# GL852-0.net
KiCad netlist of a schematic drawn in Altium Designer
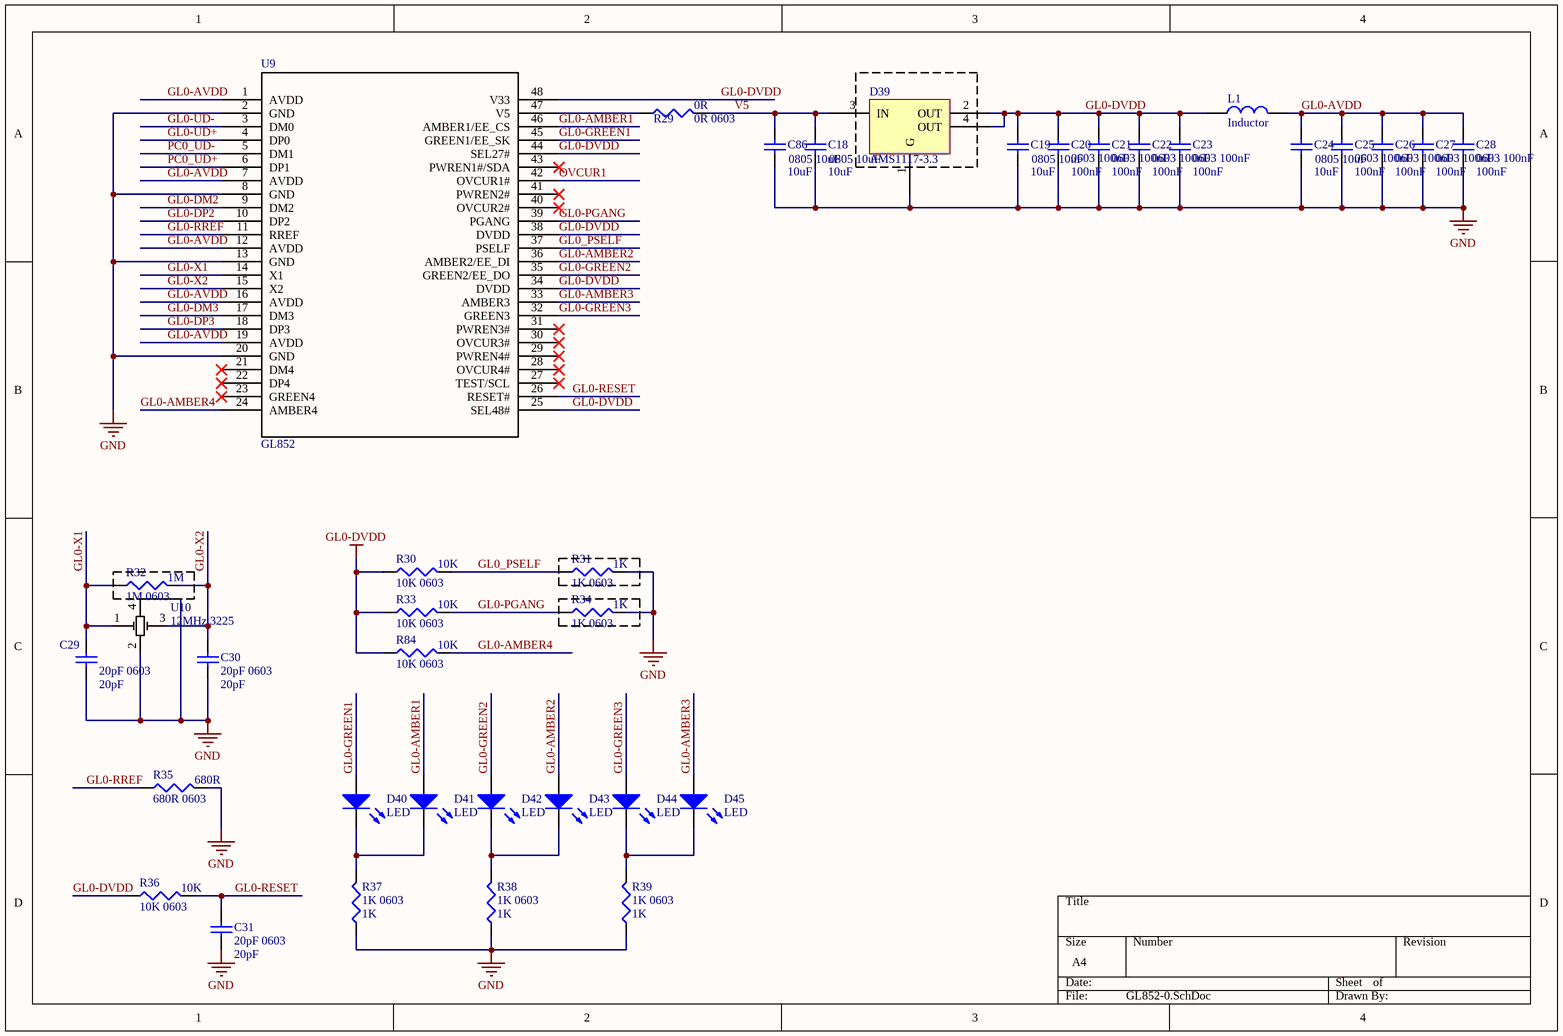
[diagram p0: GL852-0.SchDoc]

(export (version "E")
  (design (tool "Eeschema 10.0.6"))
  (components
    (comp (ref "C18")
      (value "0805 10uF")
      (footprint "C0805")
      (description "Capacitor (Semiconductor SIM Model)")
      (fields (field (name "ALTIUM_VALUE") "10uF") (field (name "PUBLISHER") "Altium Limited"))
      (libsource (lib "Miscellaneous Devices") (part "Cap Semi"))
    )
    (comp (ref "C19")
      (value "0805 10uF")
      (footprint "C0805")
      (description "Capacitor (Semiconductor SIM Model)")
      (fields (field (name "ALTIUM_VALUE") "10uF") (field (name "PUBLISHER") "Altium Limited"))
      (libsource (lib "Miscellaneous Devices") (part "Cap Semi"))
    )
    (comp (ref "C20")
      (value "0603 100nF")
      (footprint "C0603")
      (description "Capacitor (Semiconductor SIM Model)")
      (fields (field (name "ALTIUM_VALUE") "100nF") (field (name "PUBLISHER") "Altium Limited"))
      (libsource (lib "Miscellaneous Devices") (part "Cap Semi"))
    )
    (comp (ref "C21")
      (value "0603 100nF")
      (footprint "C0603")
      (description "Capacitor (Semiconductor SIM Model)")
      (fields (field (name "ALTIUM_VALUE") "100nF") (field (name "PUBLISHER") "Altium Limited"))
      (libsource (lib "Miscellaneous Devices") (part "Cap Semi"))
    )
    (comp (ref "C22")
      (value "0603 100nF")
      (footprint "C0603")
      (description "Capacitor (Semiconductor SIM Model)")
      (fields (field (name "ALTIUM_VALUE") "100nF") (field (name "PUBLISHER") "Altium Limited"))
      (libsource (lib "Miscellaneous Devices") (part "Cap Semi"))
    )
    (comp (ref "C23")
      (value "0603 100nF")
      (footprint "C0603")
      (description "Capacitor (Semiconductor SIM Model)")
      (fields (field (name "ALTIUM_VALUE") "100nF") (field (name "PUBLISHER") "Altium Limited"))
      (libsource (lib "Miscellaneous Devices") (part "Cap Semi"))
    )
    (comp (ref "C24")
      (value "0805 10uF")
      (footprint "C0805")
      (description "Capacitor (Semiconductor SIM Model)")
      (fields (field (name "ALTIUM_VALUE") "10uF") (field (name "PUBLISHER") "Altium Limited"))
      (libsource (lib "Miscellaneous Devices") (part "Cap Semi"))
    )
    (comp (ref "C25")
      (value "0603 100nF")
      (footprint "C0603")
      (description "Capacitor (Semiconductor SIM Model)")
      (fields (field (name "ALTIUM_VALUE") "100nF") (field (name "PUBLISHER") "Altium Limited"))
      (libsource (lib "Miscellaneous Devices") (part "Cap Semi"))
    )
    (comp (ref "C26")
      (value "0603 100nF")
      (footprint "C0603")
      (description "Capacitor (Semiconductor SIM Model)")
      (fields (field (name "ALTIUM_VALUE") "100nF") (field (name "PUBLISHER") "Altium Limited"))
      (libsource (lib "Miscellaneous Devices") (part "Cap Semi"))
    )
    (comp (ref "C27")
      (value "0603 100nF")
      (footprint "C0603")
      (description "Capacitor (Semiconductor SIM Model)")
      (fields (field (name "ALTIUM_VALUE") "100nF") (field (name "PUBLISHER") "Altium Limited"))
      (libsource (lib "Miscellaneous Devices") (part "Cap Semi"))
    )
    (comp (ref "C28")
      (value "0603 100nF")
      (footprint "C0603")
      (description "Capacitor (Semiconductor SIM Model)")
      (fields (field (name "ALTIUM_VALUE") "100nF") (field (name "PUBLISHER") "Altium Limited"))
      (libsource (lib "Miscellaneous Devices") (part "Cap Semi"))
    )
    (comp (ref "C29")
      (value "20pF 0603")
      (footprint "C0603")
      (description "Capacitor (Semiconductor SIM Model)")
      (fields (field (name "ALTIUM_VALUE") "20pF") (field (name "PUBLISHER") "Altium Limited"))
      (libsource (lib "Miscellaneous Devices") (part "Cap Semi"))
    )
    (comp (ref "C30")
      (value "20pF 0603")
      (footprint "C0603")
      (description "Capacitor (Semiconductor SIM Model)")
      (fields (field (name "ALTIUM_VALUE") "20pF") (field (name "PUBLISHER") "Altium Limited"))
      (libsource (lib "Miscellaneous Devices") (part "Cap Semi"))
    )
    (comp (ref "C31")
      (value "20pF 0603")
      (footprint "C0603")
      (description "Capacitor (Semiconductor SIM Model)")
      (fields (field (name "ALTIUM_VALUE") "20pF") (field (name "PUBLISHER") "Altium Limited"))
      (libsource (lib "Miscellaneous Devices") (part "Cap Semi"))
    )
    (comp (ref "C86")
      (value "0805 10uF")
      (footprint "C0805")
      (description "Capacitor (Semiconductor SIM Model)")
      (fields (field (name "ALTIUM_VALUE") "10uF") (field (name "PUBLISHER") "Altium Limited"))
      (libsource (lib "Miscellaneous Devices") (part "Cap Semi"))
    )
    (comp (ref "D39")
      (value "AMS1117-3.3")
      (footprint "SOT-223")
      (libsource (lib "MyLib") (part "AMS1117-3.3"))
    )
    (comp (ref "D40") (value "LED") (footprint "LED0603") (libsource (lib "Common Device") (part "LED")))
    (comp (ref "D41") (value "LED") (footprint "LED0603") (libsource (lib "Common Device") (part "LED")))
    (comp (ref "D42") (value "LED") (footprint "LED0603") (libsource (lib "Common Device") (part "LED")))
    (comp (ref "D43") (value "LED") (footprint "LED0603") (libsource (lib "Common Device") (part "LED")))
    (comp (ref "D44") (value "LED") (footprint "LED0603") (libsource (lib "Common Device") (part "LED")))
    (comp (ref "D45") (value "LED") (footprint "LED0603") (libsource (lib "Common Device") (part "LED")))
    (comp (ref "L1")
      (value "Inductor")
      (footprint "L0603")
      (libsource (lib "Common Device") (part "Inductor"))
    )
    (comp (ref "R29")
      (value "0R 0603")
      (footprint "R0603")
      (description "Resistor")
      (fields (field (name "ALTIUM_VALUE") "0R") (field (name "PUBLISHER") "Altium Limited"))
      (libsource (lib "Miscellaneous Devices") (part "Res3"))
    )
    (comp (ref "R30")
      (value "10K 0603")
      (footprint "R0603")
      (description "Resistor")
      (fields (field (name "ALTIUM_VALUE") "10K") (field (name "PUBLISHER") "Altium Limited"))
      (libsource (lib "Miscellaneous Devices") (part "Res3"))
    )
    (comp (ref "R31")
      (value "1K 0603")
      (footprint "R0603")
      (description "Resistor")
      (fields (field (name "ALTIUM_VALUE") "1K") (field (name "PUBLISHER") "Altium Limited"))
      (libsource (lib "Miscellaneous Devices") (part "Res3"))
    )
    (comp (ref "R32")
      (value "1M 0603")
      (footprint "R0603")
      (description "Resistor")
      (fields (field (name "ALTIUM_VALUE") "1M") (field (name "PUBLISHER") "Altium Limited"))
      (libsource (lib "Miscellaneous Devices") (part "Res3"))
    )
    (comp (ref "R33")
      (value "10K 0603")
      (footprint "R0603")
      (description "Resistor")
      (fields (field (name "ALTIUM_VALUE") "10K") (field (name "PUBLISHER") "Altium Limited"))
      (libsource (lib "Miscellaneous Devices") (part "Res3"))
    )
    (comp (ref "R34")
      (value "1K 0603")
      (footprint "R0603")
      (description "Resistor")
      (fields (field (name "ALTIUM_VALUE") "1K") (field (name "PUBLISHER") "Altium Limited"))
      (libsource (lib "Miscellaneous Devices") (part "Res3"))
    )
    (comp (ref "R35")
      (value "680R 0603")
      (footprint "R0603")
      (description "Resistor")
      (fields (field (name "ALTIUM_VALUE") "680R") (field (name "PUBLISHER") "Altium Limited"))
      (libsource (lib "Miscellaneous Devices") (part "Res3"))
    )
    (comp (ref "R36")
      (value "10K 0603")
      (footprint "R0603")
      (description "Resistor")
      (fields (field (name "ALTIUM_VALUE") "10K") (field (name "PUBLISHER") "Altium Limited"))
      (libsource (lib "Miscellaneous Devices") (part "Res3"))
    )
    (comp (ref "R37")
      (value "1K 0603")
      (footprint "R0603")
      (description "Resistor")
      (fields (field (name "ALTIUM_VALUE") "1K") (field (name "PUBLISHER") "Altium Limited"))
      (libsource (lib "Miscellaneous Devices") (part "Res3"))
    )
    (comp (ref "R38")
      (value "1K 0603")
      (footprint "R0603")
      (description "Resistor")
      (fields (field (name "ALTIUM_VALUE") "1K") (field (name "PUBLISHER") "Altium Limited"))
      (libsource (lib "Miscellaneous Devices") (part "Res3"))
    )
    (comp (ref "R39")
      (value "1K 0603")
      (footprint "R0603")
      (description "Resistor")
      (fields (field (name "ALTIUM_VALUE") "1K") (field (name "PUBLISHER") "Altium Limited"))
      (libsource (lib "Miscellaneous Devices") (part "Res3"))
    )
    (comp (ref "R84")
      (value "10K 0603")
      (footprint "R0603")
      (description "Resistor")
      (fields (field (name "ALTIUM_VALUE") "10K") (field (name "PUBLISHER") "Altium Limited"))
      (libsource (lib "Miscellaneous Devices") (part "Res3"))
    )
    (comp (ref "U9")
      (value "GL852")
      (footprint "qfp48-20-0909b")
      (description "Imported")
      (libsource (lib "USB-new-component") (part "GL852"))
    )
    (comp (ref "U10")
      (value "12MHz 3225")
      (footprint "XTAL-3225")
      (libsource (lib "XTAL3225") (part "Component_1"))
    )
  )
  (nets
    (net (code "1") (name "/GL0-AMBER1") (class "Default")
      (node (ref "D41") (pin "1") (pinfunction "A_1") (pintype "passive"))
      (node (ref "U9") (pin "46") (pinfunction "AMBER1/EE_CS_46") (pintype "passive"))
    )
    (net (code "2") (name "/GL0-AMBER2") (class "Default")
      (node (ref "D43") (pin "1") (pinfunction "A_1") (pintype "passive"))
      (node (ref "U9") (pin "36") (pinfunction "AMBER2/EE_DI_36") (pintype "passive"))
    )
    (net (code "3") (name "/GL0-AMBER3") (class "Default")
      (node (ref "D45") (pin "1") (pinfunction "A_1") (pintype "passive"))
      (node (ref "U9") (pin "33") (pinfunction "AMBER3_33") (pintype "passive"))
    )
    (net (code "4") (name "/GL0-AMBER4") (class "Default")
      (node (ref "R84") (pin "2") (pinfunction "2_2") (pintype "passive"))
      (node (ref "U9") (pin "24") (pinfunction "AMBER4_24") (pintype "passive"))
    )
    (net (code "5") (name "/GL0-AVDD") (class "Default")
      (node (ref "C24") (pin "2") (pinfunction "2_2") (pintype "passive"))
      (node (ref "C25") (pin "2") (pinfunction "2_2") (pintype "passive"))
      (node (ref "C26") (pin "2") (pinfunction "2_2") (pintype "passive"))
      (node (ref "C27") (pin "2") (pinfunction "2_2") (pintype "passive"))
      (node (ref "C28") (pin "2") (pinfunction "2_2") (pintype "passive"))
      (node (ref "L1") (pin "2") (pinfunction "2_2") (pintype "passive"))
      (node (ref "U9") (pin "1") (pinfunction "AVDD_1") (pintype "passive"))
      (node (ref "U9") (pin "12") (pinfunction "AVDD_12") (pintype "passive"))
      (node (ref "U9") (pin "16") (pinfunction "AVDD_16") (pintype "passive"))
      (node (ref "U9") (pin "19") (pinfunction "AVDD_19") (pintype "passive"))
      (node (ref "U9") (pin "7") (pinfunction "AVDD_7") (pintype "passive"))
    )
    (net (code "6") (name "/GL0-DM2") (class "Default")
      (node (ref "U9") (pin "9") (pinfunction "DM2_9") (pintype "passive"))
    )
    (net (code "7") (name "/GL0-DM3") (class "Default")
      (node (ref "U9") (pin "17") (pinfunction "DM3_17") (pintype "passive"))
    )
    (net (code "8") (name "/GL0-DP2") (class "Default")
      (node (ref "U9") (pin "10") (pinfunction "DP2_10") (pintype "passive"))
    )
    (net (code "9") (name "/GL0-DP3") (class "Default")
      (node (ref "U9") (pin "18") (pinfunction "DP3_18") (pintype "passive"))
    )
    (net (code "10") (name "/GL0-GREEN1") (class "Default")
      (node (ref "D40") (pin "1") (pinfunction "A_1") (pintype "passive"))
      (node (ref "U9") (pin "45") (pinfunction "GREEN1/EE_SK_45") (pintype "passive"))
    )
    (net (code "11") (name "/GL0-GREEN2") (class "Default")
      (node (ref "D42") (pin "1") (pinfunction "A_1") (pintype "passive"))
      (node (ref "U9") (pin "35") (pinfunction "GREEN2/EE_DO_35") (pintype "passive"))
    )
    (net (code "12") (name "/GL0-GREEN3") (class "Default")
      (node (ref "D44") (pin "1") (pinfunction "A_1") (pintype "passive"))
      (node (ref "U9") (pin "32") (pinfunction "GREEN3_32") (pintype "passive"))
    )
    (net (code "13") (name "/GL0-PGANG") (class "Default")
      (node (ref "R33") (pin "2") (pinfunction "2_2") (pintype "passive"))
      (node (ref "R34") (pin "1") (pinfunction "1_1") (pintype "passive"))
      (node (ref "U9") (pin "39") (pinfunction "PGANG_39") (pintype "passive"))
    )
    (net (code "14") (name "/GL0-RESET") (class "Default")
      (node (ref "C31") (pin "2") (pinfunction "2_2") (pintype "passive"))
      (node (ref "R36") (pin "2") (pinfunction "2_2") (pintype "passive"))
      (node (ref "U9") (pin "26") (pinfunction "RESET#_26") (pintype "passive"))
    )
    (net (code "15") (name "/GL0-RREF") (class "Default")
      (node (ref "R35") (pin "1") (pinfunction "1_1") (pintype "passive"))
      (node (ref "U9") (pin "11") (pinfunction "RREF_11") (pintype "passive"))
    )
    (net (code "16") (name "/GL0-UD+") (class "Default")
      (node (ref "U9") (pin "4") (pinfunction "DP0_4") (pintype "passive"))
    )
    (net (code "17") (name "/GL0-UD-") (class "Default")
      (node (ref "U9") (pin "3") (pinfunction "DM0_3") (pintype "passive"))
    )
    (net (code "18") (name "/GL0-X1") (class "Default")
      (node (ref "C29") (pin "2") (pinfunction "2_2") (pintype "passive"))
      (node (ref "R32") (pin "1") (pinfunction "1_1") (pintype "passive"))
      (node (ref "U10") (pin "1") (pinfunction "1_1") (pintype "passive"))
      (node (ref "U9") (pin "14") (pinfunction "X1_14") (pintype "passive"))
    )
    (net (code "19") (name "/GL0-X2") (class "Default")
      (node (ref "C30") (pin "2") (pinfunction "2_2") (pintype "passive"))
      (node (ref "R32") (pin "2") (pinfunction "2_2") (pintype "passive"))
      (node (ref "U10") (pin "3") (pinfunction "3_3") (pintype "passive"))
      (node (ref "U9") (pin "15") (pinfunction "X2_15") (pintype "passive"))
    )
    (net (code "20") (name "/GL0_PSELF") (class "Default")
      (node (ref "R30") (pin "2") (pinfunction "2_2") (pintype "passive"))
      (node (ref "R31") (pin "1") (pinfunction "1_1") (pintype "passive"))
      (node (ref "U9") (pin "37") (pinfunction "PSELF_37") (pintype "passive"))
    )
    (net (code "21") (name "/OVCUR1") (class "Default")
      (node (ref "U9") (pin "42") (pinfunction "OVCUR1#_42") (pintype "passive"))
    )
    (net (code "22") (name "/PC0_UD+") (class "Default")
      (node (ref "U9") (pin "6") (pinfunction "DP1_6") (pintype "passive"))
    )
    (net (code "23") (name "/PC0_UD-") (class "Default")
      (node (ref "U9") (pin "5") (pinfunction "DM1_5") (pintype "passive"))
    )
    (net (code "24") (name "/V5") (class "Default")
      (node (ref "C18") (pin "2") (pinfunction "2_2") (pintype "passive"))
      (node (ref "C86") (pin "2") (pinfunction "2_2") (pintype "passive"))
      (node (ref "D39") (pin "3") (pinfunction "IN_3") (pintype "passive"))
      (node (ref "R29") (pin "2") (pinfunction "2_2") (pintype "passive"))
    )
    (net (code "25") (name "GL0-DVDD") (class "Default")
      (node (ref "C19") (pin "2") (pinfunction "2_2") (pintype "passive"))
      (node (ref "C20") (pin "2") (pinfunction "2_2") (pintype "passive"))
      (node (ref "C21") (pin "2") (pinfunction "2_2") (pintype "passive"))
      (node (ref "C22") (pin "2") (pinfunction "2_2") (pintype "passive"))
      (node (ref "C23") (pin "2") (pinfunction "2_2") (pintype "passive"))
      (node (ref "D39") (pin "2") (pinfunction "OUT_2") (pintype "passive"))
      (node (ref "D39") (pin "4") (pinfunction "OUT_4") (pintype "passive"))
      (node (ref "L1") (pin "1") (pinfunction "1_1") (pintype "passive"))
      (node (ref "R30") (pin "1") (pinfunction "1_1") (pintype "passive"))
      (node (ref "R33") (pin "1") (pinfunction "1_1") (pintype "passive"))
      (node (ref "R36") (pin "1") (pinfunction "1_1") (pintype "passive"))
      (node (ref "R84") (pin "1") (pinfunction "1_1") (pintype "passive"))
      (node (ref "U9") (pin "25") (pinfunction "SEL48#_25") (pintype "passive"))
      (node (ref "U9") (pin "34") (pinfunction "DVDD_34") (pintype "passive"))
      (node (ref "U9") (pin "38") (pinfunction "DVDD_38") (pintype "passive"))
      (node (ref "U9") (pin "44") (pinfunction "SEL27#_44") (pintype "passive"))
      (node (ref "U9") (pin "48") (pinfunction "V33_48") (pintype "passive"))
    )
    (net (code "26") (name "GND") (class "Default")
      (node (ref "C18") (pin "1") (pinfunction "1_1") (pintype "passive"))
      (node (ref "C19") (pin "1") (pinfunction "1_1") (pintype "passive"))
      (node (ref "C20") (pin "1") (pinfunction "1_1") (pintype "passive"))
      (node (ref "C21") (pin "1") (pinfunction "1_1") (pintype "passive"))
      (node (ref "C22") (pin "1") (pinfunction "1_1") (pintype "passive"))
      (node (ref "C23") (pin "1") (pinfunction "1_1") (pintype "passive"))
      (node (ref "C24") (pin "1") (pinfunction "1_1") (pintype "passive"))
      (node (ref "C25") (pin "1") (pinfunction "1_1") (pintype "passive"))
      (node (ref "C26") (pin "1") (pinfunction "1_1") (pintype "passive"))
      (node (ref "C27") (pin "1") (pinfunction "1_1") (pintype "passive"))
      (node (ref "C28") (pin "1") (pinfunction "1_1") (pintype "passive"))
      (node (ref "C29") (pin "1") (pinfunction "1_1") (pintype "passive"))
      (node (ref "C30") (pin "1") (pinfunction "1_1") (pintype "passive"))
      (node (ref "C31") (pin "1") (pinfunction "1_1") (pintype "passive"))
      (node (ref "C86") (pin "1") (pinfunction "1_1") (pintype "passive"))
      (node (ref "D39") (pin "1") (pinfunction "G_1") (pintype "passive"))
      (node (ref "R31") (pin "2") (pinfunction "2_2") (pintype "passive"))
      (node (ref "R34") (pin "2") (pinfunction "2_2") (pintype "passive"))
      (node (ref "R35") (pin "2") (pinfunction "2_2") (pintype "passive"))
      (node (ref "R37") (pin "1") (pinfunction "1_1") (pintype "passive"))
      (node (ref "R38") (pin "1") (pinfunction "1_1") (pintype "passive"))
      (node (ref "R39") (pin "1") (pinfunction "1_1") (pintype "passive"))
      (node (ref "U10") (pin "2") (pinfunction "2_2") (pintype "passive"))
      (node (ref "U10") (pin "4") (pinfunction "4_4") (pintype "passive"))
      (node (ref "U9") (pin "13") (pinfunction "GND_13") (pintype "passive"))
      (node (ref "U9") (pin "2") (pinfunction "GND_2") (pintype "passive"))
      (node (ref "U9") (pin "20") (pinfunction "GND_20") (pintype "passive"))
      (node (ref "U9") (pin "8") (pinfunction "GND_8") (pintype "passive"))
    )
    (net (code "27") (name "Net-(D40-K)") (class "Default")
      (node (ref "D40") (pin "2") (pinfunction "K_2") (pintype "passive"))
      (node (ref "D41") (pin "2") (pinfunction "K_2") (pintype "passive"))
      (node (ref "R37") (pin "2") (pinfunction "2_2") (pintype "passive"))
    )
    (net (code "28") (name "Net-(D42-K)") (class "Default")
      (node (ref "D42") (pin "2") (pinfunction "K_2") (pintype "passive"))
      (node (ref "D43") (pin "2") (pinfunction "K_2") (pintype "passive"))
      (node (ref "R38") (pin "2") (pinfunction "2_2") (pintype "passive"))
    )
    (net (code "29") (name "Net-(D44-K)") (class "Default")
      (node (ref "D44") (pin "2") (pinfunction "K_2") (pintype "passive"))
      (node (ref "D45") (pin "2") (pinfunction "K_2") (pintype "passive"))
      (node (ref "R39") (pin "2") (pinfunction "2_2") (pintype "passive"))
    )
    (net (code "30") (name "Net-(U9-V5)") (class "Default")
      (node (ref "R29") (pin "1") (pinfunction "1_1") (pintype "passive"))
      (node (ref "U9") (pin "47") (pinfunction "V5_47") (pintype "passive"))
    )
    (net (code "31") (name "unconnected-(U9-DM4-Pad21)") (class "Default")
      (node (ref "U9") (pin "21") (pinfunction "DM4_21") (pintype "passive+no_connect"))
    )
    (net (code "32") (name "unconnected-(U9-DP4-Pad22)") (class "Default")
      (node (ref "U9") (pin "22") (pinfunction "DP4_22") (pintype "passive+no_connect"))
    )
    (net (code "33") (name "unconnected-(U9-GREEN4-Pad23)") (class "Default")
      (node (ref "U9") (pin "23") (pinfunction "GREEN4_23") (pintype "passive+no_connect"))
    )
    (net (code "34") (name "unconnected-(U9-OVCUR2#-Pad40)") (class "Default")
      (node (ref "U9") (pin "40") (pinfunction "OVCUR2#_40") (pintype "passive+no_connect"))
    )
    (net (code "35") (name "unconnected-(U9-OVCUR3#-Pad30)") (class "Default")
      (node (ref "U9") (pin "30") (pinfunction "OVCUR3#_30") (pintype "passive+no_connect"))
    )
    (net (code "36") (name "unconnected-(U9-OVCUR4#-Pad28)") (class "Default")
      (node (ref "U9") (pin "28") (pinfunction "OVCUR4#_28") (pintype "passive+no_connect"))
    )
    (net (code "37") (name "unconnected-(U9-PWREN1#{slash}SDA-Pad43)") (class "Default")
      (node (ref "U9") (pin "43") (pinfunction "PWREN1#/SDA_43") (pintype "passive+no_connect"))
    )
    (net (code "38") (name "unconnected-(U9-PWREN2#-Pad41)") (class "Default")
      (node (ref "U9") (pin "41") (pinfunction "PWREN2#_41") (pintype "passive+no_connect"))
    )
    (net (code "39") (name "unconnected-(U9-PWREN3#-Pad31)") (class "Default")
      (node (ref "U9") (pin "31") (pinfunction "PWREN3#_31") (pintype "passive+no_connect"))
    )
    (net (code "40") (name "unconnected-(U9-PWREN4#-Pad29)") (class "Default")
      (node (ref "U9") (pin "29") (pinfunction "PWREN4#_29") (pintype "passive+no_connect"))
    )
    (net (code "41") (name "unconnected-(U9-TEST{slash}SCL-Pad27)") (class "Default")
      (node (ref "U9") (pin "27") (pinfunction "TEST/SCL_27") (pintype "passive+no_connect"))
    )
  )
)
